# mav_nus_adapter.net
KiCad netlist of a schematic drawn in EAGLE
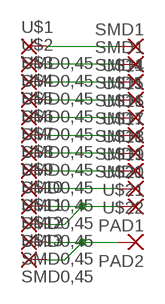
[diagram p0: schematic, sheet 1]

(export (version "E")
  (design (tool "Eeschema 10.0.6"))
  (components
    (comp (ref "PAD1")
      (value "SMD2")
      (footprint "eagle-import:SMD1,27-2,54")
      (libsource (lib "eagle-import") (part "SMD2"))
    )
    (comp (ref "PAD2")
      (value "SMD2")
      (footprint "eagle-import:SMD1,27-2,54")
      (libsource (lib "eagle-import") (part "SMD2"))
    )
    (comp (ref "U$1")
      (value "SMD0,45")
      (footprint "eagle-import:SMD0,45-1,35")
      (libsource (lib "eagle-import") (part "SMD0,45"))
    )
    (comp (ref "U$2")
      (value "SMD0,45")
      (footprint "eagle-import:SMD0,45-1,35")
      (libsource (lib "eagle-import") (part "SMD0,45"))
    )
    (comp (ref "U$3")
      (value "SMD0,45")
      (footprint "eagle-import:SMD0,45-1,35")
      (libsource (lib "eagle-import") (part "SMD0,45"))
    )
    (comp (ref "U$4")
      (value "SMD0,45")
      (footprint "eagle-import:SMD0,45-1,35")
      (libsource (lib "eagle-import") (part "SMD0,45"))
    )
    (comp (ref "U$5")
      (value "SMD0,45")
      (footprint "eagle-import:SMD0,45-1,35")
      (libsource (lib "eagle-import") (part "SMD0,45"))
    )
    (comp (ref "U$6")
      (value "SMD0,45")
      (footprint "eagle-import:SMD0,45-1,35")
      (libsource (lib "eagle-import") (part "SMD0,45"))
    )
    (comp (ref "U$7")
      (value "SMD0,45")
      (footprint "eagle-import:SMD0,45-1,35")
      (libsource (lib "eagle-import") (part "SMD0,45"))
    )
    (comp (ref "U$8")
      (value "SMD0,45")
      (footprint "eagle-import:SMD0,45-1,35")
      (libsource (lib "eagle-import") (part "SMD0,45"))
    )
    (comp (ref "U$9")
      (value "SMD0,45")
      (footprint "eagle-import:SMD0,45-1,35")
      (libsource (lib "eagle-import") (part "SMD0,45"))
    )
    (comp (ref "U$10")
      (value "SMD0,45")
      (footprint "eagle-import:SMD0,45-1,35")
      (libsource (lib "eagle-import") (part "SMD0,45"))
    )
    (comp (ref "U$11")
      (value "SMD0,45")
      (footprint "eagle-import:SMD0,45-1,35")
      (libsource (lib "eagle-import") (part "SMD0,45"))
    )
    (comp (ref "U$12")
      (value "SMD0,45")
      (footprint "eagle-import:SMD0,45-1,35")
      (libsource (lib "eagle-import") (part "SMD0,45"))
    )
    (comp (ref "U$13")
      (value "SMD0,45")
      (footprint "eagle-import:SMD0,45-1,35")
      (libsource (lib "eagle-import") (part "SMD0,45"))
    )
    (comp (ref "U$14")
      (value "SMD1")
      (footprint "eagle-import:SMD0,8-1,6")
      (libsource (lib "eagle-import") (part "SMD1"))
    )
    (comp (ref "U$15")
      (value "SMD1")
      (footprint "eagle-import:SMD0,8-1,6")
      (libsource (lib "eagle-import") (part "SMD1"))
    )
    (comp (ref "U$16")
      (value "SMD1")
      (footprint "eagle-import:SMD0,8-1,6")
      (libsource (lib "eagle-import") (part "SMD1"))
    )
    (comp (ref "U$17")
      (value "SMD1")
      (footprint "eagle-import:SMD0,8-1,6")
      (libsource (lib "eagle-import") (part "SMD1"))
    )
    (comp (ref "U$18")
      (value "SMD1")
      (footprint "eagle-import:SMD0,8-1,6")
      (libsource (lib "eagle-import") (part "SMD1"))
    )
    (comp (ref "U$19")
      (value "SMD1")
      (footprint "eagle-import:SMD0,8-1,6")
      (libsource (lib "eagle-import") (part "SMD1"))
    )
    (comp (ref "U$20")
      (value "SMD1")
      (footprint "eagle-import:SMD0,8-1,6")
      (libsource (lib "eagle-import") (part "SMD1"))
    )
    (comp (ref "U$21")
      (value "SMD1")
      (footprint "eagle-import:SMD0,8-1,6")
      (libsource (lib "eagle-import") (part "SMD1"))
    )
    (comp (ref "U$22")
      (value "SMD1")
      (footprint "eagle-import:SMD0,8-1,6")
      (libsource (lib "eagle-import") (part "SMD1"))
    )
  )
  (nets
    (net (code "1") (name "Net-(PAD1-P)") (class "Default")
      (node (ref "PAD1") (pin "1") (pinfunction "P_1") (pintype "passive"))
      (node (ref "U$10") (pin "P$1") (pinfunction "P_P$1") (pintype "passive"))
      (node (ref "U$11") (pin "P$1") (pinfunction "P_P$1") (pintype "passive"))
    )
    (net (code "2") (name "Net-(PAD2-P)") (class "Default")
      (node (ref "PAD2") (pin "1") (pinfunction "P_1") (pintype "passive"))
      (node (ref "U$12") (pin "P$1") (pinfunction "P_P$1") (pintype "passive"))
      (node (ref "U$13") (pin "P$1") (pinfunction "P_P$1") (pintype "passive"))
    )
    (net (code "3") (name "Net-(U$1-P)") (class "Default")
      (node (ref "U$1") (pin "P$1") (pinfunction "P_P$1") (pintype "passive"))
      (node (ref "U$14") (pin "P$1") (pinfunction "P_P$1") (pintype "passive"))
    )
    (net (code "4") (name "Net-(U$15-P)") (class "Default")
      (node (ref "U$15") (pin "P$1") (pinfunction "P_P$1") (pintype "passive"))
      (node (ref "U$2") (pin "P$1") (pinfunction "P_P$1") (pintype "passive"))
    )
    (net (code "5") (name "Net-(U$16-P)") (class "Default")
      (node (ref "U$16") (pin "P$1") (pinfunction "P_P$1") (pintype "passive"))
      (node (ref "U$3") (pin "P$1") (pinfunction "P_P$1") (pintype "passive"))
    )
    (net (code "6") (name "Net-(U$17-P)") (class "Default")
      (node (ref "U$17") (pin "P$1") (pinfunction "P_P$1") (pintype "passive"))
      (node (ref "U$4") (pin "P$1") (pinfunction "P_P$1") (pintype "passive"))
    )
    (net (code "7") (name "Net-(U$18-P)") (class "Default")
      (node (ref "U$18") (pin "P$1") (pinfunction "P_P$1") (pintype "passive"))
      (node (ref "U$5") (pin "P$1") (pinfunction "P_P$1") (pintype "passive"))
    )
    (net (code "8") (name "Net-(U$19-P)") (class "Default")
      (node (ref "U$19") (pin "P$1") (pinfunction "P_P$1") (pintype "passive"))
      (node (ref "U$6") (pin "P$1") (pinfunction "P_P$1") (pintype "passive"))
    )
    (net (code "9") (name "Net-(U$20-P)") (class "Default")
      (node (ref "U$20") (pin "P$1") (pinfunction "P_P$1") (pintype "passive"))
      (node (ref "U$7") (pin "P$1") (pinfunction "P_P$1") (pintype "passive"))
    )
    (net (code "10") (name "Net-(U$21-P)") (class "Default")
      (node (ref "U$21") (pin "P$1") (pinfunction "P_P$1") (pintype "passive"))
      (node (ref "U$8") (pin "P$1") (pinfunction "P_P$1") (pintype "passive"))
    )
    (net (code "11") (name "Net-(U$22-P)") (class "Default")
      (node (ref "U$22") (pin "P$1") (pinfunction "P_P$1") (pintype "passive"))
      (node (ref "U$9") (pin "P$1") (pinfunction "P_P$1") (pintype "passive"))
    )
  )
)
